# HV_Board.net
KiCad netlist of a schematic drawn in Altium Designer
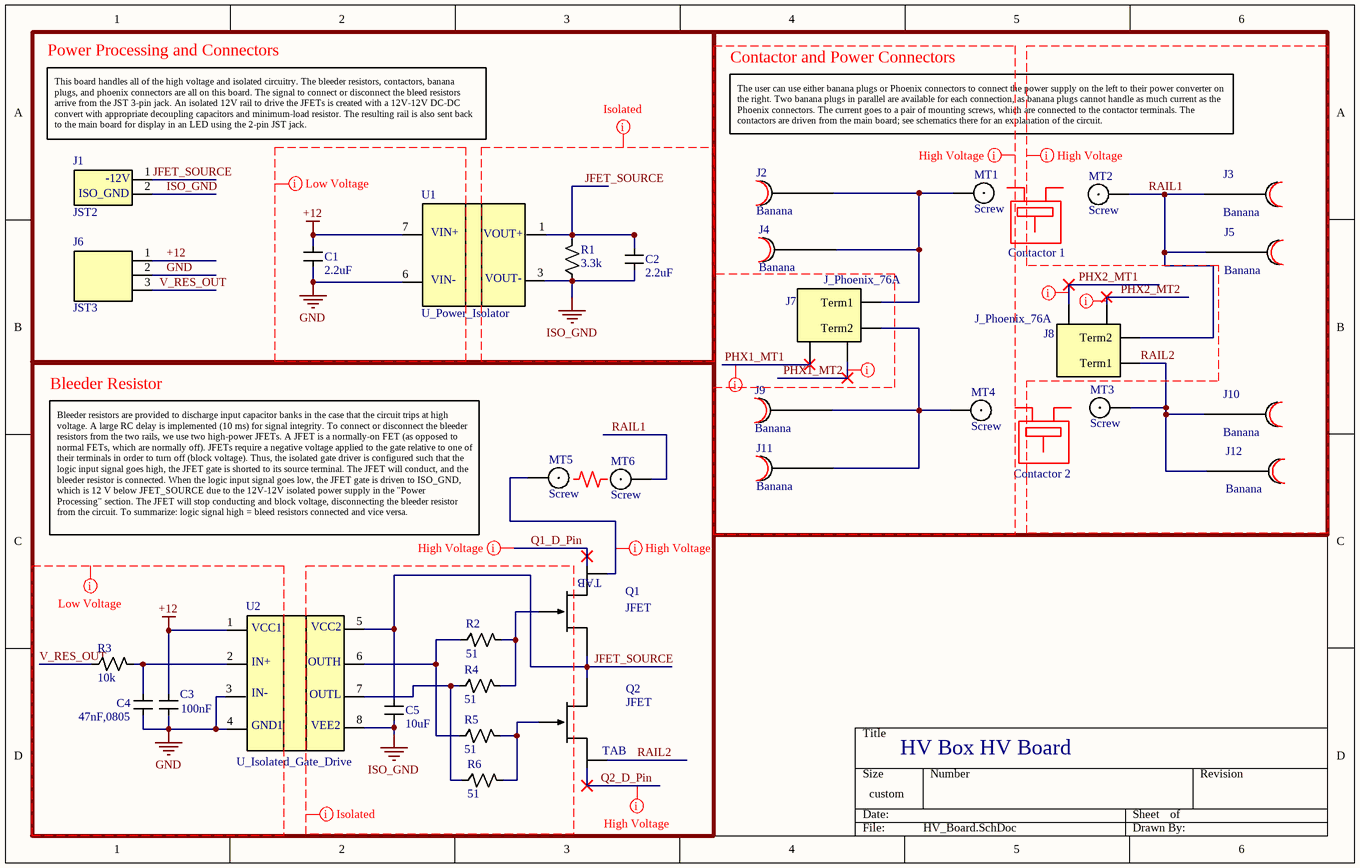
[diagram p0: HV_Board.SchDoc]

(export (version "E")
  (design (tool "Eeschema 10.0.6"))
  (components
    (comp (ref "C1")
      (value "2.2uF")
      (footprint "0603_CAP")
      (description "Capacitor SMD MLCC 2.2 uF 0603")
      (libsource (lib "Load_Bank_New_IntLib") (part "C_2.2uF_0603"))
    )
    (comp (ref "C2")
      (value "2.2uF")
      (footprint "0603_CAP")
      (description "Capacitor SMD MLCC 2.2 uF 0603")
      (libsource (lib "Load_Bank_New_IntLib") (part "C_2.2uF_0603"))
    )
    (comp (ref "C3")
      (value "100nF")
      (footprint "0603_CAP")
      (description "Capacitor SMD MLCC 100 nF 0603")
      (libsource (lib "Load_Bank_New_IntLib") (part "C_100nF_0603"))
    )
    (comp (ref "C4")
      (value "47nF,0805")
      (footprint "0805_CAP")
      (description "Capacitor SMD MLCC 47 nF 0805, C0G/NP0")
      (libsource (lib "HV_Box_IntLib") (part "C_47nF_0805"))
    )
    (comp (ref "C5")
      (value "10uF")
      (footprint "0805_CAP")
      (description "Capacitor SMD MLCC 10 uF 0805")
      (libsource (lib "Load_Bank_New_IntLib") (part "C_10uF_0805"))
    )
    (comp (ref "J1")
      (value "JST2")
      (footprint "JST_2")
      (description "Jack JST 2-pin")
      (libsource (lib "HV_Box_IntLib") (part "J_JST_2"))
    )
    (comp (ref "J2")
      (value "Banana")
      (footprint "BANANA_PLUG")
      (description "Banana Plug")
      (libsource (lib "HV_Box_IntLib") (part "J_Banana"))
    )
    (comp (ref "J3")
      (value "Banana")
      (footprint "BANANA_PLUG")
      (description "Banana Plug")
      (libsource (lib "HV_Box_IntLib") (part "J_Banana"))
    )
    (comp (ref "J4")
      (value "Banana")
      (footprint "BANANA_PLUG")
      (description "Banana Plug")
      (libsource (lib "HV_Box_IntLib") (part "J_Banana"))
    )
    (comp (ref "J5")
      (value "Banana")
      (footprint "BANANA_PLUG")
      (description "Banana Plug")
      (libsource (lib "HV_Box_IntLib") (part "J_Banana"))
    )
    (comp (ref "J6")
      (value "JST3")
      (footprint "JST_3")
      (description "Jack JST 3-pin")
      (libsource (lib "HV_Box_IntLib") (part "J_JST_3"))
    )
    (comp (ref "J7")
      (value "J_Phoenix_76A")
      (footprint "PHOENIX_CONNECTOR_76A")
      (description "Phoenix Connector, Female, 2 position, 76 A, 1 kV per position")
      (libsource (lib "HV_Box_IntLib") (part "J_Phoenix_76A"))
    )
    (comp (ref "J8")
      (value "J_Phoenix_76A")
      (footprint "PHOENIX_CONNECTOR_76A")
      (description "Phoenix Connector, Female, 2 position, 76 A, 1 kV per position")
      (libsource (lib "") (part "J_Phoenix_76A_1"))
    )
    (comp (ref "J9")
      (value "Banana")
      (footprint "BANANA_PLUG")
      (description "Banana Plug")
      (libsource (lib "HV_Box_IntLib") (part "J_Banana"))
    )
    (comp (ref "J10")
      (value "Banana")
      (footprint "BANANA_PLUG")
      (description "Banana Plug")
      (libsource (lib "HV_Box_IntLib") (part "J_Banana"))
    )
    (comp (ref "J11")
      (value "Banana")
      (footprint "BANANA_PLUG")
      (description "Banana Plug")
      (libsource (lib "HV_Box_IntLib") (part "J_Banana"))
    )
    (comp (ref "J12")
      (value "Banana")
      (footprint "BANANA_PLUG")
      (description "Banana Plug")
      (libsource (lib "HV_Box_IntLib") (part "J_Banana"))
    )
    (comp (ref "MT1")
      (value "Screw")
      (footprint "MOUNT_SMALL")
      (description "M5/M6 Screw Mount for connecting board to resistors")
      (libsource (lib "HV_Box_IntLib") (part "MT_Screw_Small"))
    )
    (comp (ref "MT2")
      (value "Screw")
      (footprint "MOUNT_SMALL")
      (description "M5/M6 Screw Mount for connecting board to resistors")
      (libsource (lib "HV_Box_IntLib") (part "MT_Screw_Small"))
    )
    (comp (ref "MT3")
      (value "Screw")
      (footprint "MOUNT_SMALL")
      (description "M5/M6 Screw Mount for connecting board to resistors")
      (libsource (lib "HV_Box_IntLib") (part "MT_Screw_Small"))
    )
    (comp (ref "MT4")
      (value "Screw")
      (footprint "MOUNT_SMALL")
      (description "M5/M6 Screw Mount for connecting board to resistors")
      (libsource (lib "HV_Box_IntLib") (part "MT_Screw_Small"))
    )
    (comp (ref "MT5")
      (value "Screw")
      (footprint "MOUNT_SMALL")
      (description "M5/M6 Screw Mount for connecting board to resistors")
      (libsource (lib "HV_Box_IntLib") (part "MT_Screw_Small"))
    )
    (comp (ref "MT6")
      (value "Screw")
      (footprint "MOUNT_SMALL")
      (description "M5/M6 Screw Mount for connecting board to resistors")
      (libsource (lib "HV_Box_IntLib") (part "MT_Screw_Small"))
    )
    (comp (ref "Q1")
      (value "JFET")
      (footprint "TO247")
      (description "N-Channel JFET1200 V 34 A TO 247-3")
      (libsource (lib "HV_Box_IntLib") (part "Q_JFET"))
    )
    (comp (ref "Q2")
      (value "JFET")
      (footprint "TO247")
      (description "N-Channel JFET1200 V 34 A TO 247-3")
      (libsource (lib "HV_Box_IntLib") (part "Q_JFET"))
    )
    (comp (ref "R1")
      (value "3.3k")
      (footprint "0603_RES")
      (description "Resistor 3.3 kOhm 0603 1%")
      (libsource (lib "Load_Bank_New_IntLib") (part "R_3300Ohm_0603_1%"))
    )
    (comp (ref "R2")
      (value "51")
      (footprint "0603_RES")
      (description "Resistor 51 Ohm 0603 1%")
      (libsource (lib "Load_Bank_New_IntLib") (part "R_51Ohm_0603_1%"))
    )
    (comp (ref "R3")
      (value "10k")
      (footprint "0603_RES")
      (description "Resistor 10 kOhm 0603 1%")
      (libsource (lib "Load_Bank_New_IntLib") (part "R_10kOhm_0603_1%"))
    )
    (comp (ref "R4")
      (value "51")
      (footprint "0603_RES")
      (description "Resistor 51 Ohm 0603 1%")
      (libsource (lib "Load_Bank_New_IntLib") (part "R_51Ohm_0603_1%"))
    )
    (comp (ref "R5")
      (value "51")
      (footprint "0603_RES")
      (description "Resistor 51 Ohm 0603 1%")
      (libsource (lib "Load_Bank_New_IntLib") (part "R_51Ohm_0603_1%"))
    )
    (comp (ref "R6")
      (value "51")
      (footprint "0603_RES")
      (description "Resistor 51 Ohm 0603 1%")
      (libsource (lib "Load_Bank_New_IntLib") (part "R_51Ohm_0603_1%"))
    )
    (comp (ref "U1")
      (value "U_Power_Isolator")
      (footprint "SIP7")
      (description "12 V -> 12 V DC-DC isolated converter, 84 mW output current, SIP7 4-lead package, 3 kV isolation")
      (libsource (lib "HV_Box_IntLib") (part "U_12_12_Power_Isolator"))
    )
    (comp (ref "U2")
      (value "U_Isolated_Gate_Drive")
      (footprint "GATE_DRIVER")
      (description "IC Isolated Gate Drive 3-15 V Output Supply Split Output")
      (libsource (lib "Load_Bank_New_IntLib") (part "U_Isolated_Gate_Drive"))
    )
  )
  (nets
    (net (code "1") (name "+12") (class "Default")
      (node (ref "C1") (pin "2") (pintype "passive"))
      (node (ref "C3") (pin "2") (pintype "passive"))
      (node (ref "J6") (pin "1") (pinfunction "Sig1_1") (pintype "passive"))
      (node (ref "U1") (pin "7") (pinfunction "Vin+_7") (pintype "passive"))
      (node (ref "U2") (pin "1") (pinfunction "VCC1_1") (pintype "passive"))
    )
    (net (code "2") (name "/JFET_SOURCE") (class "Default")
      (node (ref "C2") (pin "2") (pintype "passive"))
      (node (ref "C5") (pin "2") (pintype "passive"))
      (node (ref "J1") (pin "1") (pinfunction "Sig1_1") (pintype "passive"))
      (node (ref "Q1") (pin "3") (pinfunction "S_3") (pintype "passive"))
      (node (ref "Q2") (pin "3") (pinfunction "S_3") (pintype "passive"))
      (node (ref "R1") (pin "2") (pintype "passive"))
      (node (ref "U1") (pin "1") (pinfunction "VOUT+_1") (pintype "passive"))
      (node (ref "U2") (pin "5") (pinfunction "VCC2_5") (pintype "passive"))
    )
    (net (code "3") (name "/PHX1_MT1") (class "Default")
      (node (ref "J7") (pin "3") (pinfunction "Mt1_3") (pintype "passive+no_connect"))
    )
    (net (code "4") (name "/PHX1_MT2") (class "Default")
      (node (ref "J7") (pin "4") (pinfunction "Mt2_4") (pintype "passive+no_connect"))
    )
    (net (code "5") (name "/PHX2_MT1") (class "Default")
      (node (ref "J8") (pin "3") (pinfunction "Mt1_3") (pintype "passive+no_connect"))
    )
    (net (code "6") (name "/PHX2_MT2") (class "Default")
      (node (ref "J8") (pin "4") (pinfunction "Mt2_4") (pintype "passive+no_connect"))
    )
    (net (code "7") (name "/Q1_D_Pin") (class "Default")
      (node (ref "Q1") (pin "2") (pinfunction "D_2") (pintype "passive"))
    )
    (net (code "8") (name "/Q2_D_Pin") (class "Default")
      (node (ref "Q2") (pin "2") (pinfunction "D_2") (pintype "passive+no_connect"))
    )
    (net (code "9") (name "/RAIL1") (class "Default")
      (node (ref "J3") (pin "1") (pinfunction "Plug_1") (pintype "passive"))
      (node (ref "J5") (pin "1") (pinfunction "Plug_1") (pintype "passive"))
      (node (ref "J8") (pin "2") (pinfunction "Term2_2") (pintype "passive"))
      (node (ref "MT2") (pin "1") (pintype "passive"))
      (node (ref "MT6") (pin "1") (pintype "passive"))
    )
    (net (code "10") (name "/RAIL2") (class "Default")
      (node (ref "J10") (pin "1") (pinfunction "Plug_1") (pintype "passive"))
      (node (ref "J12") (pin "1") (pinfunction "Plug_1") (pintype "passive"))
      (node (ref "J8") (pin "1") (pinfunction "Term1_1") (pintype "passive"))
      (node (ref "MT3") (pin "1") (pintype "passive"))
      (node (ref "Q2") (pin "4") (pinfunction "TAB_4") (pintype "passive"))
    )
    (net (code "11") (name "/V_RES_OUT") (class "Default")
      (node (ref "J6") (pin "3") (pinfunction "NC_3") (pintype "passive"))
      (node (ref "R3") (pin "1") (pintype "passive"))
    )
    (net (code "12") (name "GND") (class "Default")
      (node (ref "C1") (pin "1") (pintype "passive"))
      (node (ref "C3") (pin "1") (pintype "passive"))
      (node (ref "C4") (pin "1") (pintype "passive"))
      (node (ref "J6") (pin "2") (pinfunction "Sig2_2") (pintype "passive"))
      (node (ref "U1") (pin "6") (pinfunction "VIN-_6") (pintype "passive"))
      (node (ref "U2") (pin "3") (pinfunction "IN-_3") (pintype "passive"))
      (node (ref "U2") (pin "4") (pinfunction "GND1_4") (pintype "passive"))
    )
    (net (code "13") (name "ISO_GND") (class "Default")
      (node (ref "C2") (pin "1") (pintype "passive"))
      (node (ref "C5") (pin "1") (pintype "passive"))
      (node (ref "J1") (pin "2") (pinfunction "Sig2_2") (pintype "passive"))
      (node (ref "R1") (pin "1") (pintype "passive"))
      (node (ref "U1") (pin "3") (pinfunction "VOUT-_3") (pintype "passive"))
      (node (ref "U2") (pin "8") (pinfunction "VEE2_8") (pintype "passive"))
    )
    (net (code "14") (name "Net-(J2-Plug)") (class "Default")
      (node (ref "J2") (pin "1") (pinfunction "Plug_1") (pintype "passive"))
      (node (ref "J4") (pin "1") (pinfunction "Plug_1") (pintype "passive"))
      (node (ref "J7") (pin "1") (pinfunction "Term1_1") (pintype "passive"))
      (node (ref "MT1") (pin "1") (pintype "passive"))
    )
    (net (code "15") (name "Net-(J11-Plug)") (class "Default")
      (node (ref "J11") (pin "1") (pinfunction "Plug_1") (pintype "passive"))
      (node (ref "J7") (pin "2") (pinfunction "Term2_2") (pintype "passive"))
      (node (ref "J9") (pin "1") (pinfunction "Plug_1") (pintype "passive"))
      (node (ref "MT4") (pin "1") (pintype "passive"))
    )
    (net (code "16") (name "Net-(Q1-G)") (class "Default")
      (node (ref "Q1") (pin "1") (pinfunction "G_1") (pintype "passive"))
      (node (ref "R2") (pin "2") (pintype "passive"))
      (node (ref "R4") (pin "2") (pintype "passive"))
    )
    (net (code "17") (name "Net-(Q1-TAB)") (class "Default")
      (node (ref "MT5") (pin "1") (pintype "passive"))
      (node (ref "Q1") (pin "4") (pinfunction "TAB_4") (pintype "passive"))
    )
    (net (code "18") (name "Net-(Q2-G)") (class "Default")
      (node (ref "Q2") (pin "1") (pinfunction "G_1") (pintype "passive"))
      (node (ref "R5") (pin "2") (pintype "passive"))
      (node (ref "R6") (pin "2") (pintype "passive"))
    )
    (net (code "19") (name "Net-(U2-IN+)") (class "Default")
      (node (ref "C4") (pin "2") (pintype "passive"))
      (node (ref "R3") (pin "2") (pintype "passive"))
      (node (ref "U2") (pin "2") (pinfunction "IN+_2") (pintype "passive"))
    )
    (net (code "20") (name "Net-(U2-OUTH)") (class "Default")
      (node (ref "R2") (pin "1") (pintype "passive"))
      (node (ref "R5") (pin "1") (pintype "passive"))
      (node (ref "U2") (pin "6") (pinfunction "OUTH_6") (pintype "passive"))
    )
    (net (code "21") (name "Net-(U2-OUTL)") (class "Default")
      (node (ref "R4") (pin "1") (pintype "passive"))
      (node (ref "R6") (pin "1") (pintype "passive"))
      (node (ref "U2") (pin "7") (pinfunction "OUTL_7") (pintype "passive"))
    )
  )
)
